# LPDDR4_SDRAM_1.net
KiCad netlist of a schematic drawn in Altium Designer
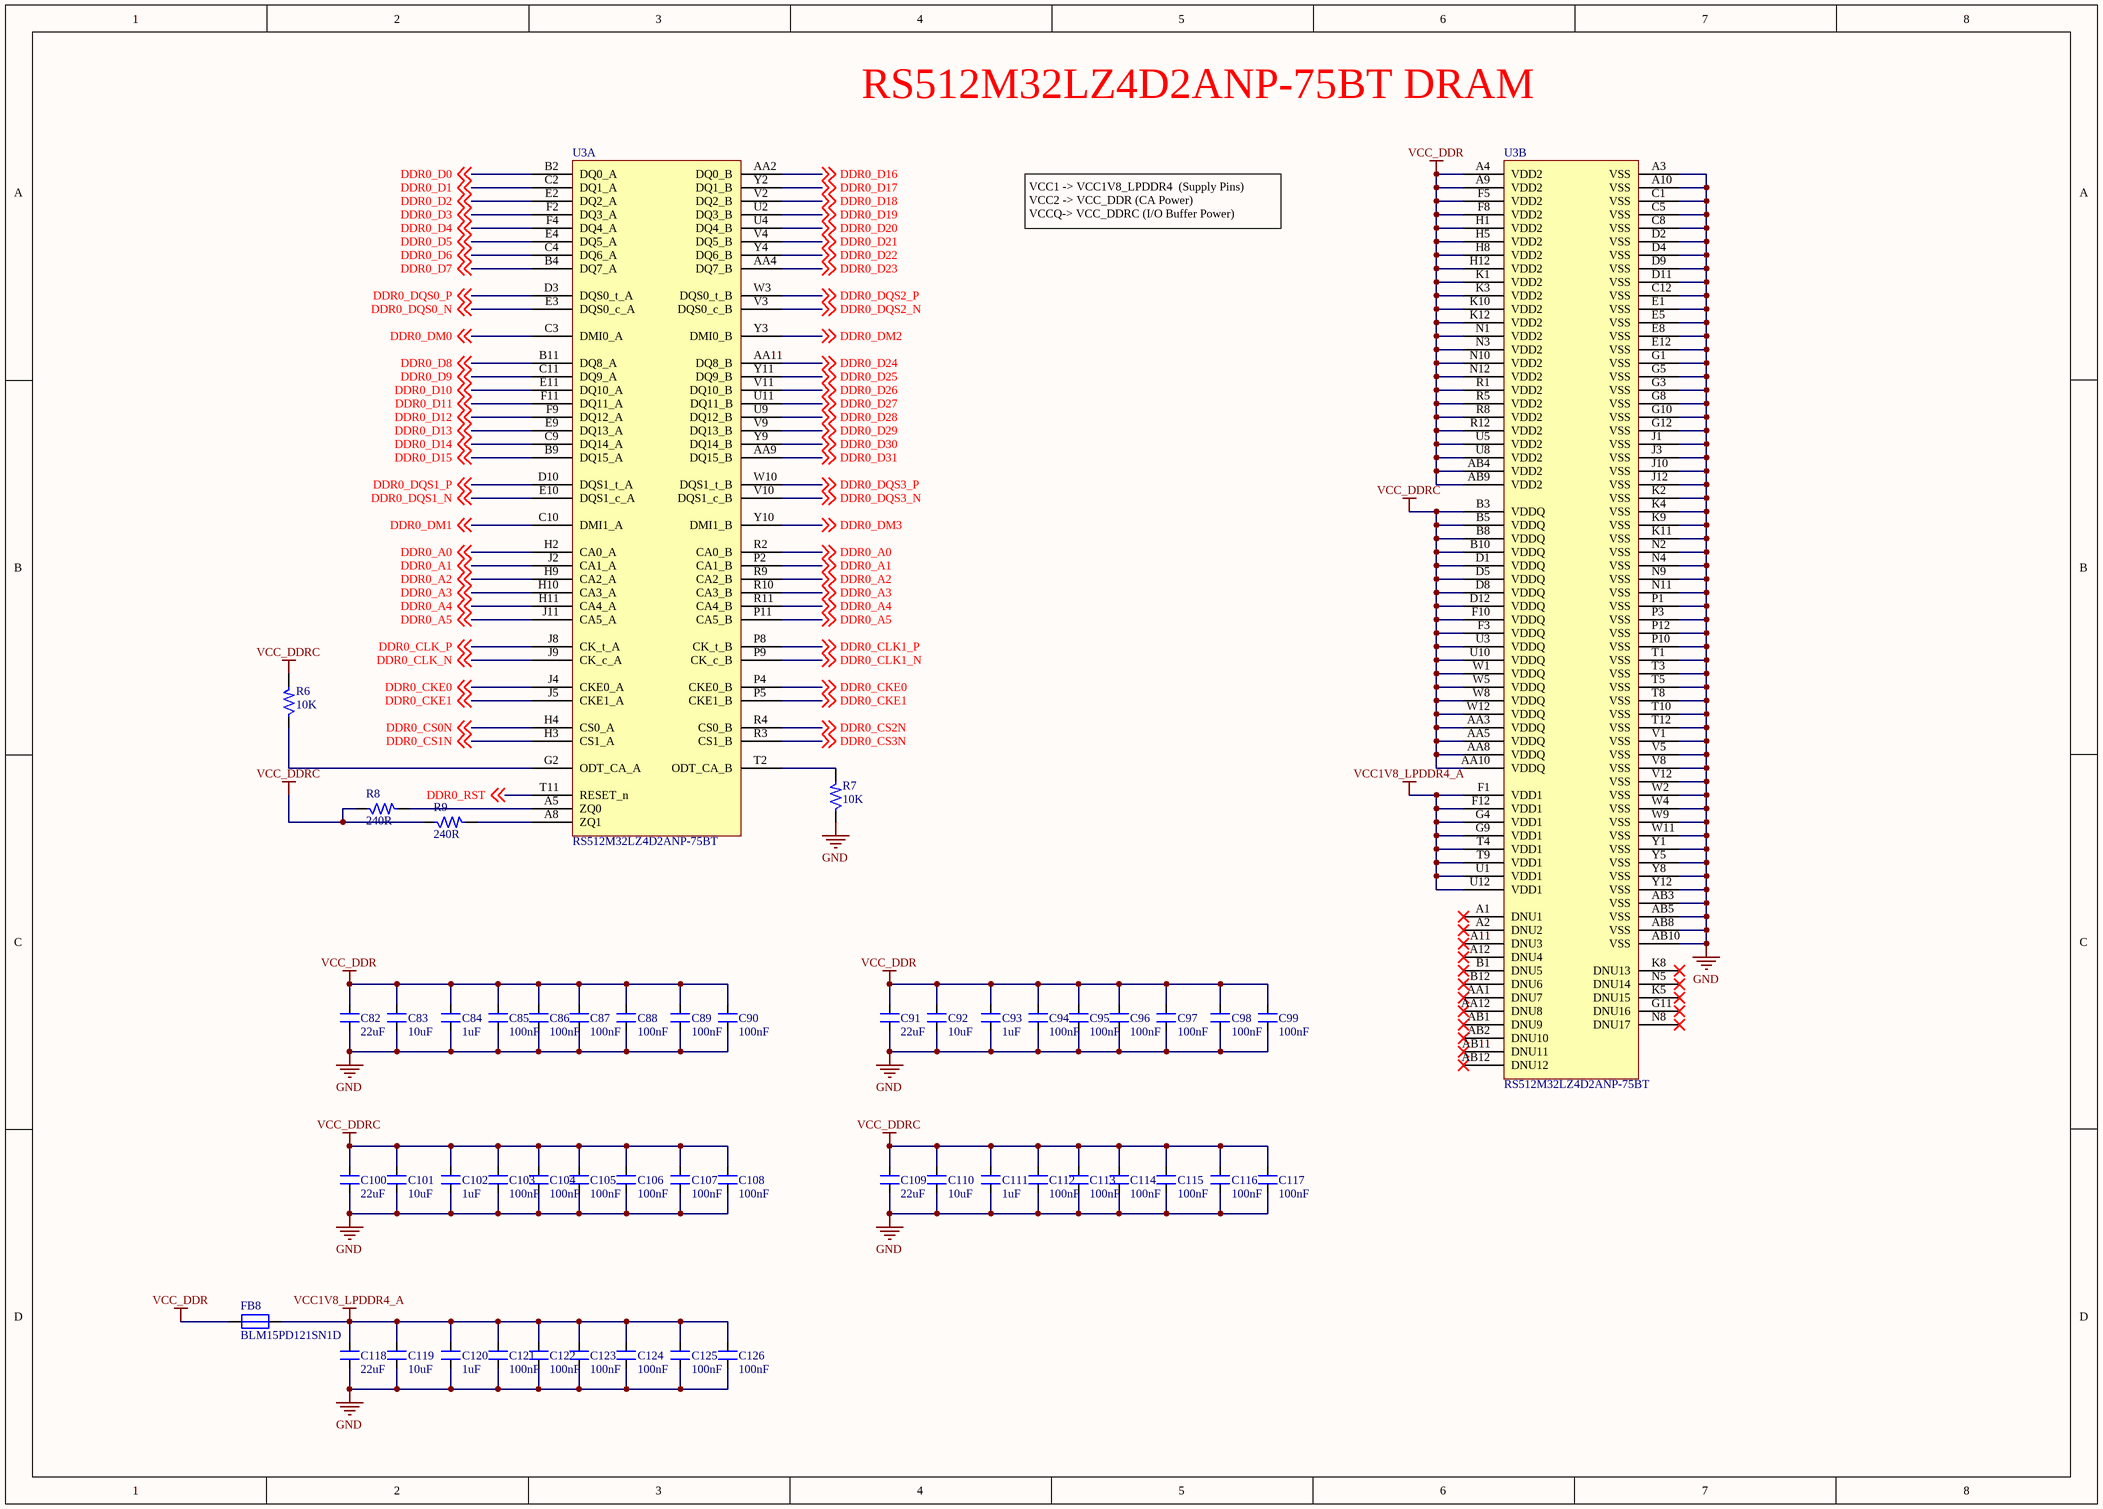
[diagram p0: LPDDR4 SDRAM_1.SchDoc]

(export (version "E")
  (design (tool "Eeschema 10.0.6"))
  (components
    (comp (ref "C82")
      (value "22uF")
      (footprint "CAP_0402")
      (description "22µF ±20% 6.3V Ceramic Capacitor X5R 0402 (1005 Metric)")
      (fields
        (field (name "MANUFACTURER") "Murata Electronics")
        (field (name "MANUFACTURER PART NUMBER") "CL05A226MQ5N6J8")
      )
      (libsource (lib "RK3399 _Module_Intlib") (part "CAP_22uF-6.3V-20%-0402"))
    )
    (comp (ref "C83")
      (value "10uF")
      (footprint "CAP_0402")
      (description "10µF ±20% 10V Ceramic Capacitor X5R 0402 (1005 Metric)")
      (fields
        (field (name "MANUFACTURER PART NUMBER") "CL05A106MP5NUNC")
        (field (name "MANUFACTURER") "Samsung Electro-Mechanics")
      )
      (libsource (lib "RK3399 _Module_Schlib") (part "CAP_10uF-10V-20%-0402"))
    )
    (comp (ref "C84")
      (value "1uF")
      (footprint "CAP_0201")
      (description "1µF ±20% 16V Ceramic Capacitor X5R 0201 (0603 Metric)")
      (fields
        (field (name "MANUFACTURER") "Samsung Electro-Mechanics")
        (field (name "MANUFACTURER PART NUMBER") "CL03A105MO3NRNH")
      )
      (libsource (lib "RK3399 _Module_Intlib") (part "CAP_1uF-16V-10%-0201"))
    )
    (comp (ref "C85")
      (value "100nF")
      (footprint "CAP_0201")
      (description "0.1µF ±10% 25V Ceramic Capacitor X5R 0201 (0603 Metric)")
      (fields
        (field (name "MANUFACTURER") "TDK Corporation")
        (field (name "MANUFACTURER PART NUMBER") "C0603X5R1E104K030BB")
      )
      (libsource (lib "RK3399 _Module_Intlib") (part "CAP_100nF-25V-10%-0201"))
    )
    (comp (ref "C86")
      (value "100nF")
      (footprint "CAP_0201")
      (description "0.1µF ±10% 25V Ceramic Capacitor X5R 0201 (0603 Metric)")
      (fields
        (field (name "MANUFACTURER") "TDK Corporation")
        (field (name "MANUFACTURER PART NUMBER") "C0603X5R1E104K030BB")
      )
      (libsource (lib "RK3399 _Module_Intlib") (part "CAP_100nF-25V-10%-0201"))
    )
    (comp (ref "C87")
      (value "100nF")
      (footprint "CAP_0201")
      (description "0.1µF ±10% 25V Ceramic Capacitor X5R 0201 (0603 Metric)")
      (fields
        (field (name "MANUFACTURER") "TDK Corporation")
        (field (name "MANUFACTURER PART NUMBER") "C0603X5R1E104K030BB")
      )
      (libsource (lib "RK3399 _Module_Intlib") (part "CAP_100nF-25V-10%-0201"))
    )
    (comp (ref "C88")
      (value "100nF")
      (footprint "CAP_0201")
      (description "0.1µF ±10% 25V Ceramic Capacitor X5R 0201 (0603 Metric)")
      (fields
        (field (name "MANUFACTURER") "TDK Corporation")
        (field (name "MANUFACTURER PART NUMBER") "C0603X5R1E104K030BB")
      )
      (libsource (lib "RK3399 _Module_Intlib") (part "CAP_100nF-25V-10%-0201"))
    )
    (comp (ref "C89")
      (value "100nF")
      (footprint "CAP_0201")
      (description "0.1µF ±10% 25V Ceramic Capacitor X5R 0201 (0603 Metric)")
      (fields
        (field (name "MANUFACTURER") "TDK Corporation")
        (field (name "MANUFACTURER PART NUMBER") "C0603X5R1E104K030BB")
      )
      (libsource (lib "RK3399 _Module_Intlib") (part "CAP_100nF-25V-10%-0201"))
    )
    (comp (ref "C90")
      (value "100nF")
      (footprint "CAP_0201")
      (description "0.1µF ±10% 25V Ceramic Capacitor X5R 0201 (0603 Metric)")
      (fields
        (field (name "MANUFACTURER") "TDK Corporation")
        (field (name "MANUFACTURER PART NUMBER") "C0603X5R1E104K030BB")
      )
      (libsource (lib "RK3399 _Module_Intlib") (part "CAP_100nF-25V-10%-0201"))
    )
    (comp (ref "C91")
      (value "22uF")
      (footprint "CAP_0402")
      (description "22µF ±20% 6.3V Ceramic Capacitor X5R 0402 (1005 Metric)")
      (fields
        (field (name "MANUFACTURER") "Murata Electronics")
        (field (name "MANUFACTURER PART NUMBER") "CL05A226MQ5N6J8")
      )
      (libsource (lib "RK3399 _Module_Intlib") (part "CAP_22uF-6.3V-20%-0402"))
    )
    (comp (ref "C92")
      (value "10uF")
      (footprint "CAP_0402")
      (description "10µF ±20% 10V Ceramic Capacitor X5R 0402 (1005 Metric)")
      (fields
        (field (name "MANUFACTURER PART NUMBER") "CL05A106MP5NUNC")
        (field (name "MANUFACTURER") "Samsung Electro-Mechanics")
      )
      (libsource (lib "RK3399 _Module_Schlib") (part "CAP_10uF-10V-20%-0402"))
    )
    (comp (ref "C93")
      (value "1uF")
      (footprint "CAP_0201")
      (description "1µF ±20% 16V Ceramic Capacitor X5R 0201 (0603 Metric)")
      (fields
        (field (name "MANUFACTURER") "Samsung Electro-Mechanics")
        (field (name "MANUFACTURER PART NUMBER") "CL03A105MO3NRNH")
      )
      (libsource (lib "RK3399 _Module_Intlib") (part "CAP_1uF-16V-10%-0201"))
    )
    (comp (ref "C94")
      (value "100nF")
      (footprint "CAP_0201")
      (description "0.1µF ±10% 25V Ceramic Capacitor X5R 0201 (0603 Metric)")
      (fields
        (field (name "MANUFACTURER") "TDK Corporation")
        (field (name "MANUFACTURER PART NUMBER") "C0603X5R1E104K030BB")
      )
      (libsource (lib "RK3399 _Module_Intlib") (part "CAP_100nF-25V-10%-0201"))
    )
    (comp (ref "C95")
      (value "100nF")
      (footprint "CAP_0201")
      (description "0.1µF ±10% 25V Ceramic Capacitor X5R 0201 (0603 Metric)")
      (fields
        (field (name "MANUFACTURER") "TDK Corporation")
        (field (name "MANUFACTURER PART NUMBER") "C0603X5R1E104K030BB")
      )
      (libsource (lib "RK3399 _Module_Intlib") (part "CAP_100nF-25V-10%-0201"))
    )
    (comp (ref "C96")
      (value "100nF")
      (footprint "CAP_0201")
      (description "0.1µF ±10% 25V Ceramic Capacitor X5R 0201 (0603 Metric)")
      (fields
        (field (name "MANUFACTURER") "TDK Corporation")
        (field (name "MANUFACTURER PART NUMBER") "C0603X5R1E104K030BB")
      )
      (libsource (lib "RK3399 _Module_Intlib") (part "CAP_100nF-25V-10%-0201"))
    )
    (comp (ref "C97")
      (value "100nF")
      (footprint "CAP_0201")
      (description "0.1µF ±10% 25V Ceramic Capacitor X5R 0201 (0603 Metric)")
      (fields
        (field (name "MANUFACTURER") "TDK Corporation")
        (field (name "MANUFACTURER PART NUMBER") "C0603X5R1E104K030BB")
      )
      (libsource (lib "RK3399 _Module_Intlib") (part "CAP_100nF-25V-10%-0201"))
    )
    (comp (ref "C98")
      (value "100nF")
      (footprint "CAP_0201")
      (description "0.1µF ±10% 25V Ceramic Capacitor X5R 0201 (0603 Metric)")
      (fields
        (field (name "MANUFACTURER") "TDK Corporation")
        (field (name "MANUFACTURER PART NUMBER") "C0603X5R1E104K030BB")
      )
      (libsource (lib "RK3399 _Module_Intlib") (part "CAP_100nF-25V-10%-0201"))
    )
    (comp (ref "C99")
      (value "100nF")
      (footprint "CAP_0201")
      (description "0.1µF ±10% 25V Ceramic Capacitor X5R 0201 (0603 Metric)")
      (fields
        (field (name "MANUFACTURER") "TDK Corporation")
        (field (name "MANUFACTURER PART NUMBER") "C0603X5R1E104K030BB")
      )
      (libsource (lib "RK3399 _Module_Intlib") (part "CAP_100nF-25V-10%-0201"))
    )
    (comp (ref "C100")
      (value "22uF")
      (footprint "CAP_0402")
      (description "22µF ±20% 6.3V Ceramic Capacitor X5R 0402 (1005 Metric)")
      (fields
        (field (name "MANUFACTURER") "Murata Electronics")
        (field (name "MANUFACTURER PART NUMBER") "CL05A226MQ5N6J8")
      )
      (libsource (lib "RK3399 _Module_Intlib") (part "CAP_22uF-6.3V-20%-0402"))
    )
    (comp (ref "C101")
      (value "10uF")
      (footprint "CAP_0402")
      (description "10µF ±20% 10V Ceramic Capacitor X5R 0402 (1005 Metric)")
      (fields
        (field (name "MANUFACTURER PART NUMBER") "CL05A106MP5NUNC")
        (field (name "MANUFACTURER") "Samsung Electro-Mechanics")
      )
      (libsource (lib "RK3399 _Module_Schlib") (part "CAP_10uF-10V-20%-0402"))
    )
    (comp (ref "C102")
      (value "1uF")
      (footprint "CAP_0201")
      (description "1µF ±20% 16V Ceramic Capacitor X5R 0201 (0603 Metric)")
      (fields
        (field (name "MANUFACTURER") "Samsung Electro-Mechanics")
        (field (name "MANUFACTURER PART NUMBER") "CL03A105MO3NRNH")
      )
      (libsource (lib "RK3399 _Module_Intlib") (part "CAP_1uF-16V-10%-0201"))
    )
    (comp (ref "C103")
      (value "100nF")
      (footprint "CAP_0201")
      (description "0.1µF ±10% 25V Ceramic Capacitor X5R 0201 (0603 Metric)")
      (fields
        (field (name "MANUFACTURER") "TDK Corporation")
        (field (name "MANUFACTURER PART NUMBER") "C0603X5R1E104K030BB")
      )
      (libsource (lib "RK3399 _Module_Intlib") (part "CAP_100nF-25V-10%-0201"))
    )
    (comp (ref "C104")
      (value "100nF")
      (footprint "CAP_0201")
      (description "0.1µF ±10% 25V Ceramic Capacitor X5R 0201 (0603 Metric)")
      (fields
        (field (name "MANUFACTURER") "TDK Corporation")
        (field (name "MANUFACTURER PART NUMBER") "C0603X5R1E104K030BB")
      )
      (libsource (lib "RK3399 _Module_Intlib") (part "CAP_100nF-25V-10%-0201"))
    )
    (comp (ref "C105")
      (value "100nF")
      (footprint "CAP_0201")
      (description "0.1µF ±10% 25V Ceramic Capacitor X5R 0201 (0603 Metric)")
      (fields
        (field (name "MANUFACTURER") "TDK Corporation")
        (field (name "MANUFACTURER PART NUMBER") "C0603X5R1E104K030BB")
      )
      (libsource (lib "RK3399 _Module_Intlib") (part "CAP_100nF-25V-10%-0201"))
    )
    (comp (ref "C106")
      (value "100nF")
      (footprint "CAP_0201")
      (description "0.1µF ±10% 25V Ceramic Capacitor X5R 0201 (0603 Metric)")
      (fields
        (field (name "MANUFACTURER") "TDK Corporation")
        (field (name "MANUFACTURER PART NUMBER") "C0603X5R1E104K030BB")
      )
      (libsource (lib "RK3399 _Module_Intlib") (part "CAP_100nF-25V-10%-0201"))
    )
    (comp (ref "C107")
      (value "100nF")
      (footprint "CAP_0201")
      (description "0.1µF ±10% 25V Ceramic Capacitor X5R 0201 (0603 Metric)")
      (fields
        (field (name "MANUFACTURER") "TDK Corporation")
        (field (name "MANUFACTURER PART NUMBER") "C0603X5R1E104K030BB")
      )
      (libsource (lib "RK3399 _Module_Intlib") (part "CAP_100nF-25V-10%-0201"))
    )
    (comp (ref "C108")
      (value "100nF")
      (footprint "CAP_0201")
      (description "0.1µF ±10% 25V Ceramic Capacitor X5R 0201 (0603 Metric)")
      (fields
        (field (name "MANUFACTURER") "TDK Corporation")
        (field (name "MANUFACTURER PART NUMBER") "C0603X5R1E104K030BB")
      )
      (libsource (lib "RK3399 _Module_Intlib") (part "CAP_100nF-25V-10%-0201"))
    )
    (comp (ref "C109")
      (value "22uF")
      (footprint "CAP_0402")
      (description "22µF ±20% 6.3V Ceramic Capacitor X5R 0402 (1005 Metric)")
      (fields
        (field (name "MANUFACTURER") "Murata Electronics")
        (field (name "MANUFACTURER PART NUMBER") "CL05A226MQ5N6J8")
      )
      (libsource (lib "RK3399 _Module_Intlib") (part "CAP_22uF-6.3V-20%-0402"))
    )
    (comp (ref "C110")
      (value "10uF")
      (footprint "CAP_0402")
      (description "10µF ±20% 10V Ceramic Capacitor X5R 0402 (1005 Metric)")
      (fields
        (field (name "MANUFACTURER PART NUMBER") "CL05A106MP5NUNC")
        (field (name "MANUFACTURER") "Samsung Electro-Mechanics")
      )
      (libsource (lib "RK3399 _Module_Schlib") (part "CAP_10uF-10V-20%-0402"))
    )
    (comp (ref "C111")
      (value "1uF")
      (footprint "CAP_0201")
      (description "1µF ±20% 16V Ceramic Capacitor X5R 0201 (0603 Metric)")
      (fields
        (field (name "MANUFACTURER") "Samsung Electro-Mechanics")
        (field (name "MANUFACTURER PART NUMBER") "CL03A105MO3NRNH")
      )
      (libsource (lib "RK3399 _Module_Intlib") (part "CAP_1uF-16V-10%-0201"))
    )
    (comp (ref "C112")
      (value "100nF")
      (footprint "CAP_0201")
      (description "0.1µF ±10% 25V Ceramic Capacitor X5R 0201 (0603 Metric)")
      (fields
        (field (name "MANUFACTURER") "TDK Corporation")
        (field (name "MANUFACTURER PART NUMBER") "C0603X5R1E104K030BB")
      )
      (libsource (lib "RK3399 _Module_Intlib") (part "CAP_100nF-25V-10%-0201"))
    )
    (comp (ref "C113")
      (value "100nF")
      (footprint "CAP_0201")
      (description "0.1µF ±10% 25V Ceramic Capacitor X5R 0201 (0603 Metric)")
      (fields
        (field (name "MANUFACTURER") "TDK Corporation")
        (field (name "MANUFACTURER PART NUMBER") "C0603X5R1E104K030BB")
      )
      (libsource (lib "RK3399 _Module_Intlib") (part "CAP_100nF-25V-10%-0201"))
    )
    (comp (ref "C114")
      (value "100nF")
      (footprint "CAP_0201")
      (description "0.1µF ±10% 25V Ceramic Capacitor X5R 0201 (0603 Metric)")
      (fields
        (field (name "MANUFACTURER") "TDK Corporation")
        (field (name "MANUFACTURER PART NUMBER") "C0603X5R1E104K030BB")
      )
      (libsource (lib "RK3399 _Module_Intlib") (part "CAP_100nF-25V-10%-0201"))
    )
    (comp (ref "C115")
      (value "100nF")
      (footprint "CAP_0201")
      (description "0.1µF ±10% 25V Ceramic Capacitor X5R 0201 (0603 Metric)")
      (fields
        (field (name "MANUFACTURER") "TDK Corporation")
        (field (name "MANUFACTURER PART NUMBER") "C0603X5R1E104K030BB")
      )
      (libsource (lib "RK3399 _Module_Intlib") (part "CAP_100nF-25V-10%-0201"))
    )
    (comp (ref "C116")
      (value "100nF")
      (footprint "CAP_0201")
      (description "0.1µF ±10% 25V Ceramic Capacitor X5R 0201 (0603 Metric)")
      (fields
        (field (name "MANUFACTURER") "TDK Corporation")
        (field (name "MANUFACTURER PART NUMBER") "C0603X5R1E104K030BB")
      )
      (libsource (lib "RK3399 _Module_Intlib") (part "CAP_100nF-25V-10%-0201"))
    )
    (comp (ref "C117")
      (value "100nF")
      (footprint "CAP_0201")
      (description "0.1µF ±10% 25V Ceramic Capacitor X5R 0201 (0603 Metric)")
      (fields
        (field (name "MANUFACTURER") "TDK Corporation")
        (field (name "MANUFACTURER PART NUMBER") "C0603X5R1E104K030BB")
      )
      (libsource (lib "RK3399 _Module_Intlib") (part "CAP_100nF-25V-10%-0201"))
    )
    (comp (ref "C118")
      (value "22uF")
      (footprint "CAP_0402")
      (description "22µF ±20% 6.3V Ceramic Capacitor X5R 0402 (1005 Metric)")
      (fields
        (field (name "MANUFACTURER") "Murata Electronics")
        (field (name "MANUFACTURER PART NUMBER") "CL05A226MQ5N6J8")
      )
      (libsource (lib "RK3399 _Module_Intlib") (part "CAP_22uF-6.3V-20%-0402"))
    )
    (comp (ref "C119")
      (value "10uF")
      (footprint "CAP_0402")
      (description "10µF ±20% 10V Ceramic Capacitor X5R 0402 (1005 Metric)")
      (fields
        (field (name "MANUFACTURER PART NUMBER") "CL05A106MP5NUNC")
        (field (name "MANUFACTURER") "Samsung Electro-Mechanics")
      )
      (libsource (lib "RK3399 _Module_Schlib") (part "CAP_10uF-10V-20%-0402"))
    )
    (comp (ref "C120")
      (value "1uF")
      (footprint "CAP_0201")
      (description "1µF ±20% 16V Ceramic Capacitor X5R 0201 (0603 Metric)")
      (fields
        (field (name "MANUFACTURER") "Samsung Electro-Mechanics")
        (field (name "MANUFACTURER PART NUMBER") "CL03A105MO3NRNH")
      )
      (libsource (lib "RK3399 _Module_Intlib") (part "CAP_1uF-16V-10%-0201"))
    )
    (comp (ref "C121")
      (value "100nF")
      (footprint "CAP_0201")
      (description "0.1µF ±10% 25V Ceramic Capacitor X5R 0201 (0603 Metric)")
      (fields
        (field (name "MANUFACTURER") "TDK Corporation")
        (field (name "MANUFACTURER PART NUMBER") "C0603X5R1E104K030BB")
      )
      (libsource (lib "RK3399 _Module_Intlib") (part "CAP_100nF-25V-10%-0201"))
    )
    (comp (ref "C122")
      (value "100nF")
      (footprint "CAP_0201")
      (description "0.1µF ±10% 25V Ceramic Capacitor X5R 0201 (0603 Metric)")
      (fields
        (field (name "MANUFACTURER") "TDK Corporation")
        (field (name "MANUFACTURER PART NUMBER") "C0603X5R1E104K030BB")
      )
      (libsource (lib "RK3399 _Module_Intlib") (part "CAP_100nF-25V-10%-0201"))
    )
    (comp (ref "C123")
      (value "100nF")
      (footprint "CAP_0201")
      (description "0.1µF ±10% 25V Ceramic Capacitor X5R 0201 (0603 Metric)")
      (fields
        (field (name "MANUFACTURER") "TDK Corporation")
        (field (name "MANUFACTURER PART NUMBER") "C0603X5R1E104K030BB")
      )
      (libsource (lib "RK3399 _Module_Intlib") (part "CAP_100nF-25V-10%-0201"))
    )
    (comp (ref "C124")
      (value "100nF")
      (footprint "CAP_0201")
      (description "0.1µF ±10% 25V Ceramic Capacitor X5R 0201 (0603 Metric)")
      (fields
        (field (name "MANUFACTURER") "TDK Corporation")
        (field (name "MANUFACTURER PART NUMBER") "C0603X5R1E104K030BB")
      )
      (libsource (lib "RK3399 _Module_Intlib") (part "CAP_100nF-25V-10%-0201"))
    )
    (comp (ref "C125")
      (value "100nF")
      (footprint "CAP_0201")
      (description "0.1µF ±10% 25V Ceramic Capacitor X5R 0201 (0603 Metric)")
      (fields
        (field (name "MANUFACTURER") "TDK Corporation")
        (field (name "MANUFACTURER PART NUMBER") "C0603X5R1E104K030BB")
      )
      (libsource (lib "RK3399 _Module_Intlib") (part "CAP_100nF-25V-10%-0201"))
    )
    (comp (ref "C126")
      (value "100nF")
      (footprint "CAP_0201")
      (description "0.1µF ±10% 25V Ceramic Capacitor X5R 0201 (0603 Metric)")
      (fields
        (field (name "MANUFACTURER") "TDK Corporation")
        (field (name "MANUFACTURER PART NUMBER") "C0603X5R1E104K030BB")
      )
      (libsource (lib "RK3399 _Module_Intlib") (part "CAP_100nF-25V-10%-0201"))
    )
    (comp (ref "FB8")
      (value "BLM15PD121SN1D")
      (footprint "RES_0402")
      (description "120 Ohms @ 100MHz 1 Power Line Ferrite Bead 0402 (1005 Metric) 1.3A 90mOhm")
      (fields (field (name "MANUFACTURER") "Murata Electronics"))
      (libsource (lib "RK3399 _Module_Schlib") (part "FB_120R-1.3A-100Mhz-0402"))
    )
    (comp (ref "R6")
      (value "10K")
      (footprint "RES_0201")
      (description "10 kOhms ±1% 0.05W, 1/20W Chip Resistor 0201 (0603 Metric) Thick Film")
      (fields
        (field (name "MANUFACTURER") "Stackpole Electronics Inc")
        (field (name "MANUFACTURER PART NUMBER") "RMCF0201FT10K0")
      )
      (libsource (lib "RK3399 _Module_Intlib") (part "RES_10K-0.05W-1%-0201"))
    )
    (comp (ref "R7")
      (value "10K")
      (footprint "RES_0201")
      (description "10 kOhms ±1% 0.05W, 1/20W Chip Resistor 0201 (0603 Metric) Thick Film")
      (fields
        (field (name "MANUFACTURER") "Stackpole Electronics Inc")
        (field (name "MANUFACTURER PART NUMBER") "RMCF0201FT10K0")
      )
      (libsource (lib "RK3399 _Module_Intlib") (part "RES_10K-0.05W-1%-0201"))
    )
    (comp (ref "R8")
      (value "240R")
      (footprint "RES_0201")
      (description "240 Ohms ±1% 0.05W, 1/20W Chip Resistor 0201 (0603 Metric) Thick Film")
      (fields
        (field (name "MANUFACTURER") "Yageo")
        (field (name "MANUFACTURER PART NUMBER") "RC0201FR-07240RL")
      )
      (libsource (lib "RK3399 _Module_Intlib") (part "RES_240R-0.05W-1%-0201"))
    )
    (comp (ref "R9")
      (value "240R")
      (footprint "RES_0201")
      (description "240 Ohms ±1% 0.05W, 1/20W Chip Resistor 0201 (0603 Metric) Thick Film")
      (fields
        (field (name "MANUFACTURER") "Yageo")
        (field (name "MANUFACTURER PART NUMBER") "RC0201FR-07240RL")
      )
      (libsource (lib "RK3399 _Module_Intlib") (part "RES_240R-0.05W-1%-0201"))
    )
    (comp (ref "U3")
      (value "RS512M32LZ4D2ANP-75BT")
      (footprint "FBGA200_SMD")
      (fields (field (name "MANUFACTURER") "RAYSON"))
      (libsource (lib "RK3399 _Module_Schlib") (part "IC_RS512M32LZ4D2ANP-75BT"))
    )
  )
  (nets
    (net (code "1") (name "DDR0_A0") (class "Default")
      (node (ref "U3") (pin "H2") (pinfunction "CA0_A_H2") (pintype "passive"))
      (node (ref "U3") (pin "R2") (pinfunction "CA0_B_R2") (pintype "passive"))
    )
    (net (code "2") (name "DDR0_A1") (class "Default")
      (node (ref "U3") (pin "J2") (pinfunction "CA1_A_J2") (pintype "passive"))
      (node (ref "U3") (pin "P2") (pinfunction "CA1_B_P2") (pintype "passive"))
    )
    (net (code "3") (name "DDR0_A2") (class "Default")
      (node (ref "U3") (pin "H9") (pinfunction "CA2_A_H9") (pintype "passive"))
      (node (ref "U3") (pin "R9") (pinfunction "CA2_B_R9") (pintype "passive"))
    )
    (net (code "4") (name "DDR0_A3") (class "Default")
      (node (ref "U3") (pin "H10") (pinfunction "CA3_A_H10") (pintype "passive"))
      (node (ref "U3") (pin "R10") (pinfunction "CA3_B_R10") (pintype "passive"))
    )
    (net (code "5") (name "DDR0_A4") (class "Default")
      (node (ref "U3") (pin "H11") (pinfunction "CA4_A_H11") (pintype "passive"))
      (node (ref "U3") (pin "R11") (pinfunction "CA4_B_R11") (pintype "passive"))
    )
    (net (code "6") (name "DDR0_A5") (class "Default")
      (node (ref "U3") (pin "J11") (pinfunction "CA5_A_J11") (pintype "passive"))
      (node (ref "U3") (pin "P11") (pinfunction "CA5_B_P11") (pintype "passive"))
    )
    (net (code "7") (name "DDR0_CKE0") (class "Default")
      (node (ref "U3") (pin "J4") (pinfunction "CKE0_A_J4") (pintype "passive"))
      (node (ref "U3") (pin "P4") (pinfunction "CKE0_B_P4") (pintype "passive"))
    )
    (net (code "8") (name "DDR0_CKE1") (class "Default")
      (node (ref "U3") (pin "J5") (pinfunction "CKE1_A_J5") (pintype "passive"))
      (node (ref "U3") (pin "P5") (pinfunction "CKE1_B_P5") (pintype "passive"))
    )
    (net (code "9") (name "DDR0_CLK1_N") (class "Default")
      (node (ref "U3") (pin "P9") (pinfunction "CK_c_B_P9") (pintype "passive"))
    )
    (net (code "10") (name "DDR0_CLK1_P") (class "Default")
      (node (ref "U3") (pin "P8") (pinfunction "CK_t_B_P8") (pintype "passive"))
    )
    (net (code "11") (name "DDR0_CLK_N") (class "Default")
      (node (ref "U3") (pin "J9") (pinfunction "CK_c_A_J9") (pintype "passive"))
    )
    (net (code "12") (name "DDR0_CLK_P") (class "Default")
      (node (ref "U3") (pin "J8") (pinfunction "CK_t_A_J8") (pintype "passive"))
    )
    (net (code "13") (name "DDR0_CS0N") (class "Default")
      (node (ref "U3") (pin "H4") (pinfunction "CS0_A_H4") (pintype "passive"))
    )
    (net (code "14") (name "DDR0_CS1N") (class "Default")
      (node (ref "U3") (pin "H3") (pinfunction "CS1_A_H3") (pintype "passive"))
    )
    (net (code "15") (name "DDR0_CS2N") (class "Default")
      (node (ref "U3") (pin "R4") (pinfunction "CS0_B_R4") (pintype "passive"))
    )
    (net (code "16") (name "DDR0_CS3N") (class "Default")
      (node (ref "U3") (pin "R3") (pinfunction "CS1_B_R3") (pintype "passive"))
    )
    (net (code "17") (name "DDR0_D0") (class "Default")
      (node (ref "U3") (pin "B2") (pinfunction "DQ0_A_B2") (pintype "passive"))
    )
    (net (code "18") (name "DDR0_D1") (class "Default")
      (node (ref "U3") (pin "C2") (pinfunction "DQ1_A_C2") (pintype "passive"))
    )
    (net (code "19") (name "DDR0_D2") (class "Default")
      (node (ref "U3") (pin "E2") (pinfunction "DQ2_A_E2") (pintype "passive"))
    )
    (net (code "20") (name "DDR0_D3") (class "Default")
      (node (ref "U3") (pin "F2") (pinfunction "DQ3_A_F2") (pintype "passive"))
    )
    (net (code "21") (name "DDR0_D4") (class "Default")
      (node (ref "U3") (pin "F4") (pinfunction "DQ4_A_F4") (pintype "passive"))
    )
    (net (code "22") (name "DDR0_D5") (class "Default")
      (node (ref "U3") (pin "E4") (pinfunction "DQ5_A_E4") (pintype "passive"))
    )
    (net (code "23") (name "DDR0_D6") (class "Default")
      (node (ref "U3") (pin "C4") (pinfunction "DQ6_A_C4") (pintype "passive"))
    )
    (net (code "24") (name "DDR0_D7") (class "Default")
      (node (ref "U3") (pin "B4") (pinfunction "DQ7_A_B4") (pintype "passive"))
    )
    (net (code "25") (name "DDR0_D8") (class "Default")
      (node (ref "U3") (pin "B11") (pinfunction "DQ8_A_B11") (pintype "passive"))
    )
    (net (code "26") (name "DDR0_D9") (class "Default")
      (node (ref "U3") (pin "C11") (pinfunction "DQ9_A_C11") (pintype "passive"))
    )
    (net (code "27") (name "DDR0_D10") (class "Default")
      (node (ref "U3") (pin "E11") (pinfunction "DQ10_A_E11") (pintype "passive"))
    )
    (net (code "28") (name "DDR0_D11") (class "Default")
      (node (ref "U3") (pin "F11") (pinfunction "DQ11_A_F11") (pintype "passive"))
    )
    (net (code "29") (name "DDR0_D12") (class "Default")
      (node (ref "U3") (pin "F9") (pinfunction "DQ12_A_F9") (pintype "passive"))
    )
    (net (code "30") (name "DDR0_D13") (class "Default")
      (node (ref "U3") (pin "E9") (pinfunction "DQ13_A_E9") (pintype "passive"))
    )
    (net (code "31") (name "DDR0_D14") (class "Default")
      (node (ref "U3") (pin "C9") (pinfunction "DQ14_A_C9") (pintype "passive"))
    )
    (net (code "32") (name "DDR0_D15") (class "Default")
      (node (ref "U3") (pin "B9") (pinfunction "DQ15_A_B9") (pintype "passive"))
    )
    (net (code "33") (name "DDR0_D16") (class "Default")
      (node (ref "U3") (pin "AA2") (pinfunction "DQ0_B_AA2") (pintype "passive"))
    )
    (net (code "34") (name "DDR0_D17") (class "Default")
      (node (ref "U3") (pin "Y2") (pinfunction "DQ1_B_Y2") (pintype "passive"))
    )
    (net (code "35") (name "DDR0_D18") (class "Default")
      (node (ref "U3") (pin "V2") (pinfunction "DQ2_B_V2") (pintype "passive"))
    )
    (net (code "36") (name "DDR0_D19") (class "Default")
      (node (ref "U3") (pin "U2") (pinfunction "DQ3_B_U2") (pintype "passive"))
    )
    (net (code "37") (name "DDR0_D20") (class "Default")
      (node (ref "U3") (pin "U4") (pinfunction "DQ4_B_U4") (pintype "passive"))
    )
    (net (code "38") (name "DDR0_D21") (class "Default")
      (node (ref "U3") (pin "V4") (pinfunction "DQ5_B_V4") (pintype "passive"))
    )
    (net (code "39") (name "DDR0_D22") (class "Default")
      (node (ref "U3") (pin "Y4") (pinfunction "DQ6_B_Y4") (pintype "passive"))
    )
    (net (code "40") (name "DDR0_D23") (class "Default")
      (node (ref "U3") (pin "AA4") (pinfunction "DQ7_B_AA4") (pintype "passive"))
    )
    (net (code "41") (name "DDR0_D24") (class "Default")
      (node (ref "U3") (pin "AA11") (pinfunction "DQ8_B_AA11") (pintype "passive"))
    )
    (net (code "42") (name "DDR0_D25") (class "Default")
      (node (ref "U3") (pin "Y11") (pinfunction "DQ9_B_Y11") (pintype "passive"))
    )
    (net (code "43") (name "DDR0_D26") (class "Default")
      (node (ref "U3") (pin "V11") (pinfunction "DQ10_B_V11") (pintype "passive"))
    )
    (net (code "44") (name "DDR0_D27") (class "Default")
      (node (ref "U3") (pin "U11") (pinfunction "DQ11_B_U11") (pintype "passive"))
    )
    (net (code "45") (name "DDR0_D28") (class "Default")
      (node (ref "U3") (pin "U9") (pinfunction "DQ12_B_U9") (pintype "passive"))
    )
    (net (code "46") (name "DDR0_D29") (class "Default")
      (node (ref "U3") (pin "V9") (pinfunction "DQ13_B_V9") (pintype "passive"))
    )
    (net (code "47") (name "DDR0_D30") (class "Default")
      (node (ref "U3") (pin "Y9") (pinfunction "DQ14_B_Y9") (pintype "passive"))
    )
    (net (code "48") (name "DDR0_D31") (class "Default")
      (node (ref "U3") (pin "AA9") (pinfunction "DQ15_B_AA9") (pintype "passive"))
    )
    (net (code "49") (name "DDR0_DM0") (class "Default")
      (node (ref "U3") (pin "C3") (pinfunction "DMI0_A_C3") (pintype "passive"))
    )
    (net (code "50") (name "DDR0_DM1") (class "Default")
      (node (ref "U3") (pin "C10") (pinfunction "DMI1_A_C10") (pintype "passive"))
    )
    (net (code "51") (name "DDR0_DM2") (class "Default")
      (node (ref "U3") (pin "Y3") (pinfunction "DMI0_B_Y3") (pintype "passive"))
    )
    (net (code "52") (name "DDR0_DM3") (class "Default")
      (node (ref "U3") (pin "Y10") (pinfunction "DMI1_B_Y10") (pintype "passive"))
    )
    (net (code "53") (name "DDR0_DQS0_N") (class "Default")
      (node (ref "U3") (pin "E3") (pinfunction "DQS0_c_A_E3") (pintype "passive"))
    )
    (net (code "54") (name "DDR0_DQS0_P") (class "Default")
      (node (ref "U3") (pin "D3") (pinfunction "DQS0_t_A_D3") (pintype "passive"))
    )
    (net (code "55") (name "DDR0_DQS1_N") (class "Default")
      (node (ref "U3") (pin "E10") (pinfunction "DQS1_c_A_E10") (pintype "passive"))
    )
    (net (code "56") (name "DDR0_DQS1_P") (class "Default")
      (node (ref "U3") (pin "D10") (pinfunction "DQS1_t_A_D10") (pintype "passive"))
    )
    (net (code "57") (name "DDR0_DQS2_N") (class "Default")
      (node (ref "U3") (pin "V3") (pinfunction "DQS0_c_B_V3") (pintype "passive"))
    )
    (net (code "58") (name "DDR0_DQS2_P") (class "Default")
      (node (ref "U3") (pin "W3") (pinfunction "DQS0_t_B_W3") (pintype "passive"))
    )
    (net (code "59") (name "DDR0_DQS3_N") (class "Default")
      (node (ref "U3") (pin "V10") (pinfunction "DQS1_c_B_V10") (pintype "passive"))
    )
    (net (code "60") (name "DDR0_DQS3_P") (class "Default")
      (node (ref "U3") (pin "W10") (pinfunction "DQS1_t_B_W10") (pintype "passive"))
    )
    (net (code "61") (name "DDR0_RST") (class "Default")
      (node (ref "U3") (pin "T11") (pinfunction "RESET_n_T11") (pintype "passive"))
    )
    (net (code "62") (name "GND") (class "Default")
      (node (ref "C100") (pin "1") (pinfunction "1_1") (pintype "passive"))
      (node (ref "C101") (pin "1") (pinfunction "1_1") (pintype "passive"))
      (node (ref "C102") (pin "1") (pinfunction "1_1") (pintype "passive"))
      (node (ref "C103") (pin "1") (pinfunction "1_1") (pintype "passive"))
      (node (ref "C104") (pin "1") (pinfunction "1_1") (pintype "passive"))
      (node (ref "C105") (pin "1") (pinfunction "1_1") (pintype "passive"))
      (node (ref "C106") (pin "1") (pinfunction "1_1") (pintype "passive"))
      (node (ref "C107") (pin "1") (pinfunction "1_1") (pintype "passive"))
      (node (ref "C108") (pin "1") (pinfunction "1_1") (pintype "passive"))
      (node (ref "C109") (pin "1") (pinfunction "1_1") (pintype "passive"))
      (node (ref "C110") (pin "1") (pinfunction "1_1") (pintype "passive"))
      (node (ref "C111") (pin "1") (pinfunction "1_1") (pintype "passive"))
      (node (ref "C112") (pin "1") (pinfunction "1_1") (pintype "passive"))
      (node (ref "C113") (pin "1") (pinfunction "1_1") (pintype "passive"))
      (node (ref "C114") (pin "1") (pinfunction "1_1") (pintype "passive"))
      (node (ref "C115") (pin "1") (pinfunction "1_1") (pintype "passive"))
      (node (ref "C116") (pin "1") (pinfunction "1_1") (pintype "passive"))
      (node (ref "C117") (pin "1") (pinfunction "1_1") (pintype "passive"))
      (node (ref "C118") (pin "1") (pinfunction "1_1") (pintype "passive"))
      (node (ref "C119") (pin "1") (pinfunction "1_1") (pintype "passive"))
      (node (ref "C120") (pin "1") (pinfunction "1_1") (pintype "passive"))
      (node (ref "C121") (pin "1") (pinfunction "1_1") (pintype "passive"))
      (node (ref "C122") (pin "1") (pinfunction "1_1") (pintype "passive"))
      (node (ref "C123") (pin "1") (pinfunction "1_1") (pintype "passive"))
      (node (ref "C124") (pin "1") (pinfunction "1_1") (pintype "passive"))
      (node (ref "C125") (pin "1") (pinfunction "1_1") (pintype "passive"))
      (node (ref "C126") (pin "1") (pinfunction "1_1") (pintype "passive"))
      (node (ref "C82") (pin "1") (pinfunction "1_1") (pintype "passive"))
      (node (ref "C83") (pin "1") (pinfunction "1_1") (pintype "passive"))
      (node (ref "C84") (pin "1") (pinfunction "1_1") (pintype "passive"))
      (node (ref "C85") (pin "1") (pinfunction "1_1") (pintype "passive"))
      (node (ref "C86") (pin "1") (pinfunction "1_1") (pintype "passive"))
      (node (ref "C87") (pin "1") (pinfunction "1_1") (pintype "passive"))
      (node (ref "C88") (pin "1") (pinfunction "1_1") (pintype "passive"))
      (node (ref "C89") (pin "1") (pinfunction "1_1") (pintype "passive"))
      (node (ref "C90") (pin "1") (pinfunction "1_1") (pintype "passive"))
      (node (ref "C91") (pin "1") (pinfunction "1_1") (pintype "passive"))
      (node (ref "C92") (pin "1") (pinfunction "1_1") (pintype "passive"))
      (node (ref "C93") (pin "1") (pinfunction "1_1") (pintype "passive"))
      (node (ref "C94") (pin "1") (pinfunction "1_1") (pintype "passive"))
      (node (ref "C95") (pin "1") (pinfunction "1_1") (pintype "passive"))
      (node (ref "C96") (pin "1") (pinfunction "1_1") (pintype "passive"))
      (node (ref "C97") (pin "1") (pinfunction "1_1") (pintype "passive"))
      (node (ref "C98") (pin "1") (pinfunction "1_1") (pintype "passive"))
      (node (ref "C99") (pin "1") (pinfunction "1_1") (pintype "passive"))
      (node (ref "R7") (pin "1") (pinfunction "1_1") (pintype "passive"))
      (node (ref "U3") (pin "A10") (pinfunction "VSS_A10") (pintype "passive"))
      (node (ref "U3") (pin "A3") (pinfunction "VSS_A3") (pintype "passive"))
      (node (ref "U3") (pin "AB10") (pinfunction "VSS_AB10") (pintype "passive"))
      (node (ref "U3") (pin "AB3") (pinfunction "VSS_AB3") (pintype "passive"))
      (node (ref "U3") (pin "AB5") (pinfunction "VSS_AB5") (pintype "passive"))
      (node (ref "U3") (pin "AB8") (pinfunction "VSS_AB8") (pintype "passive"))
      (node (ref "U3") (pin "C1") (pinfunction "VSS_C1") (pintype "passive"))
      (node (ref "U3") (pin "C12") (pinfunction "VSS_C12") (pintype "passive"))
      (node (ref "U3") (pin "C5") (pinfunction "VSS_C5") (pintype "passive"))
      (node (ref "U3") (pin "C8") (pinfunction "VSS_C8") (pintype "passive"))
      (node (ref "U3") (pin "D11") (pinfunction "VSS_D11") (pintype "passive"))
      (node (ref "U3") (pin "D2") (pinfunction "VSS_D2") (pintype "passive"))
      (node (ref "U3") (pin "D4") (pinfunction "VSS_D4") (pintype "passive"))
      (node (ref "U3") (pin "D9") (pinfunction "VSS_D9") (pintype "passive"))
      (node (ref "U3") (pin "E1") (pinfunction "VSS_E1") (pintype "passive"))
      (node (ref "U3") (pin "E12") (pinfunction "VSS_E12") (pintype "passive"))
      (node (ref "U3") (pin "E5") (pinfunction "VSS_E5") (pintype "passive"))
      (node (ref "U3") (pin "E8") (pinfunction "VSS_E8") (pintype "passive"))
      (node (ref "U3") (pin "G1") (pinfunction "VSS_G1") (pintype "passive"))
      (node (ref "U3") (pin "G10") (pinfunction "VSS_G10") (pintype "passive"))
      (node (ref "U3") (pin "G12") (pinfunction "VSS_G12") (pintype "passive"))
      (node (ref "U3") (pin "G3") (pinfunction "VSS_G3") (pintype "passive"))
      (node (ref "U3") (pin "G5") (pinfunction "VSS_G5") (pintype "passive"))
      (node (ref "U3") (pin "G8") (pinfunction "VSS_G8") (pintype "passive"))
      (node (ref "U3") (pin "J1") (pinfunction "VSS_J1") (pintype "passive"))
      (node (ref "U3") (pin "J10") (pinfunction "VSS_J10") (pintype "passive"))
      (node (ref "U3") (pin "J12") (pinfunction "VSS_J12") (pintype "passive"))
      (node (ref "U3") (pin "J3") (pinfunction "VSS_J3") (pintype "passive"))
      (node (ref "U3") (pin "K11") (pinfunction "VSS_K11") (pintype "passive"))
      (node (ref "U3") (pin "K2") (pinfunction "VSS_K2") (pintype "passive"))
      (node (ref "U3") (pin "K4") (pinfunction "VSS_K4") (pintype "passive"))
      (node (ref "U3") (pin "K9") (pinfunction "VSS_K9") (pintype "passive"))
      (node (ref "U3") (pin "N11") (pinfunction "VSS_N11") (pintype "passive"))
      (node (ref "U3") (pin "N2") (pinfunction "VSS_N2") (pintype "passive"))
      (node (ref "U3") (pin "N4") (pinfunction "VSS_N4") (pintype "passive"))
      (node (ref "U3") (pin "N9") (pinfunction "VSS_N9") (pintype "passive"))
      (node (ref "U3") (pin "P1") (pinfunction "VSS_P1") (pintype "passive"))
      (node (ref "U3") (pin "P10") (pinfunction "VSS_P10") (pintype "passive"))
      (node (ref "U3") (pin "P12") (pinfunction "VSS_P12") (pintype "passive"))
      (node (ref "U3") (pin "P3") (pinfunction "VSS_P3") (pintype "passive"))
      (node (ref "U3") (pin "T1") (pinfunction "VSS_T1") (pintype "passive"))
      (node (ref "U3") (pin "T10") (pinfunction "VSS_T10") (pintype "passive"))
      (node (ref "U3") (pin "T12") (pinfunction "VSS_T12") (pintype "passive"))
      (node (ref "U3") (pin "T3") (pinfunction "VSS_T3") (pintype "passive"))
      (node (ref "U3") (pin "T5") (pinfunction "VSS_T5") (pintype "passive"))
      (node (ref "U3") (pin "T8") (pinfunction "VSS_T8") (pintype "passive"))
      (node (ref "U3") (pin "V1") (pinfunction "VSS_V1") (pintype "passive"))
      (node (ref "U3") (pin "V12") (pinfunction "VSS_V12") (pintype "passive"))
      (node (ref "U3") (pin "V5") (pinfunction "VSS_V5") (pintype "passive"))
      (node (ref "U3") (pin "V8") (pinfunction "VSS_V8") (pintype "passive"))
      (node (ref "U3") (pin "W11") (pinfunction "VSS_W11") (pintype "passive"))
      (node (ref "U3") (pin "W2") (pinfunction "VSS_W2") (pintype "passive"))
      (node (ref "U3") (pin "W4") (pinfunction "VSS_W4") (pintype "passive"))
      (node (ref "U3") (pin "W9") (pinfunction "VSS_W9") (pintype "passive"))
      (node (ref "U3") (pin "Y1") (pinfunction "VSS_Y1") (pintype "passive"))
      (node (ref "U3") (pin "Y12") (pinfunction "VSS_Y12") (pintype "passive"))
      (node (ref "U3") (pin "Y5") (pinfunction "VSS_Y5") (pintype "passive"))
      (node (ref "U3") (pin "Y8") (pinfunction "VSS_Y8") (pintype "passive"))
    )
    (net (code "63") (name "Net-(U3A-ODT_CA_A)") (class "Default")
      (node (ref "R6") (pin "1") (pinfunction "1_1") (pintype "passive"))
      (node (ref "U3") (pin "G2") (pinfunction "ODT_CA_A_G2") (pintype "passive"))
    )
    (net (code "64") (name "Net-(U3A-ODT_CA_B)") (class "Default")
      (node (ref "R7") (pin "2") (pinfunction "2_2") (pintype "passive"))
      (node (ref "U3") (pin "T2") (pinfunction "ODT_CA_B_T2") (pintype "passive"))
    )
    (net (code "65") (name "Net-(U3A-ZQ0)") (class "Default")
      (node (ref "R8") (pin "2") (pinfunction "2_2") (pintype "passive"))
      (node (ref "U3") (pin "A5") (pinfunction "ZQ0_A5") (pintype "passive"))
    )
    (net (code "66") (name "Net-(U3A-ZQ1)") (class "Default")
      (node (ref "R9") (pin "2") (pinfunction "2_2") (pintype "passive"))
      (node (ref "U3") (pin "A8") (pinfunction "ZQ1_A8") (pintype "passive"))
    )
    (net (code "67") (name "VCC1V8_LPDDR4_A") (class "Default")
      (node (ref "C118") (pin "2") (pinfunction "2_2") (pintype "passive"))
      (node (ref "C119") (pin "2") (pinfunction "2_2") (pintype "passive"))
      (node (ref "C120") (pin "2") (pinfunction "2_2") (pintype "passive"))
      (node (ref "C121") (pin "2") (pinfunction "2_2") (pintype "passive"))
      (node (ref "C122") (pin "2") (pinfunction "2_2") (pintype "passive"))
      (node (ref "C123") (pin "2") (pinfunction "2_2") (pintype "passive"))
      (node (ref "C124") (pin "2") (pinfunction "2_2") (pintype "passive"))
      (node (ref "C125") (pin "2") (pinfunction "2_2") (pintype "passive"))
      (node (ref "C126") (pin "2") (pinfunction "2_2") (pintype "passive"))
      (node (ref "FB8") (pin "2") (pinfunction "2_2") (pintype "passive"))
      (node (ref "U3") (pin "F1") (pinfunction "VDD1_F1") (pintype "passive"))
      (node (ref "U3") (pin "F12") (pinfunction "VDD1_F12") (pintype "passive"))
      (node (ref "U3") (pin "G4") (pinfunction "VDD1_G4") (pintype "passive"))
      (node (ref "U3") (pin "G9") (pinfunction "VDD1_G9") (pintype "passive"))
      (node (ref "U3") (pin "T4") (pinfunction "VDD1_T4") (pintype "passive"))
      (node (ref "U3") (pin "T9") (pinfunction "VDD1_T9") (pintype "passive"))
      (node (ref "U3") (pin "U1") (pinfunction "VDD1_U1") (pintype "passive"))
      (node (ref "U3") (pin "U12") (pinfunction "VDD1_U12") (pintype "passive"))
    )
    (net (code "68") (name "VCC_DDR") (class "Default")
      (node (ref "C82") (pin "2") (pinfunction "2_2") (pintype "passive"))
      (node (ref "C83") (pin "2") (pinfunction "2_2") (pintype "passive"))
      (node (ref "C84") (pin "2") (pinfunction "2_2") (pintype "passive"))
      (node (ref "C85") (pin "2") (pinfunction "2_2") (pintype "passive"))
      (node (ref "C86") (pin "2") (pinfunction "2_2") (pintype "passive"))
      (node (ref "C87") (pin "2") (pinfunction "2_2") (pintype "passive"))
      (node (ref "C88") (pin "2") (pinfunction "2_2") (pintype "passive"))
      (node (ref "C89") (pin "2") (pinfunction "2_2") (pintype "passive"))
      (node (ref "C90") (pin "2") (pinfunction "2_2") (pintype "passive"))
      (node (ref "C91") (pin "2") (pinfunction "2_2") (pintype "passive"))
      (node (ref "C92") (pin "2") (pinfunction "2_2") (pintype "passive"))
      (node (ref "C93") (pin "2") (pinfunction "2_2") (pintype "passive"))
      (node (ref "C94") (pin "2") (pinfunction "2_2") (pintype "passive"))
      (node (ref "C95") (pin "2") (pinfunction "2_2") (pintype "passive"))
      (node (ref "C96") (pin "2") (pinfunction "2_2") (pintype "passive"))
      (node (ref "C97") (pin "2") (pinfunction "2_2") (pintype "passive"))
      (node (ref "C98") (pin "2") (pinfunction "2_2") (pintype "passive"))
      (node (ref "C99") (pin "2") (pinfunction "2_2") (pintype "passive"))
      (node (ref "FB8") (pin "1") (pinfunction "1_1") (pintype "passive"))
      (node (ref "U3") (pin "A4") (pinfunction "VDD2_A4") (pintype "passive"))
      (node (ref "U3") (pin "A9") (pinfunction "VDD2_A9") (pintype "passive"))
      (node (ref "U3") (pin "AB4") (pinfunction "VDD2_AB4") (pintype "passive"))
      (node (ref "U3") (pin "AB9") (pinfunction "VDD2_AB9") (pintype "passive"))
      (node (ref "U3") (pin "F5") (pinfunction "VDD2_F5") (pintype "passive"))
      (node (ref "U3") (pin "F8") (pinfunction "VDD2_F8") (pintype "passive"))
      (node (ref "U3") (pin "H1") (pinfunction "VDD2_H1") (pintype "passive"))
      (node (ref "U3") (pin "H12") (pinfunction "VDD2_H12") (pintype "passive"))
      (node (ref "U3") (pin "H5") (pinfunction "VDD2_H5") (pintype "passive"))
      (node (ref "U3") (pin "H8") (pinfunction "VDD2_H8") (pintype "passive"))
      (node (ref "U3") (pin "K1") (pinfunction "VDD2_K1") (pintype "passive"))
      (node (ref "U3") (pin "K10") (pinfunction "VDD2_K10") (pintype "passive"))
      (node (ref "U3") (pin "K12") (pinfunction "VDD2_K12") (pintype "passive"))
      (node (ref "U3") (pin "K3") (pinfunction "VDD2_K3") (pintype "passive"))
      (node (ref "U3") (pin "N1") (pinfunction "VDD2_N1") (pintype "passive"))
      (node (ref "U3") (pin "N10") (pinfunction "VDD2_N10") (pintype "passive"))
      (node (ref "U3") (pin "N12") (pinfunction "VDD2_N12") (pintype "passive"))
      (node (ref "U3") (pin "N3") (pinfunction "VDD2_N3") (pintype "passive"))
      (node (ref "U3") (pin "R1") (pinfunction "VDD2_R1") (pintype "passive"))
      (node (ref "U3") (pin "R12") (pinfunction "VDD2_R12") (pintype "passive"))
      (node (ref "U3") (pin "R5") (pinfunction "VDD2_R5") (pintype "passive"))
      (node (ref "U3") (pin "R8") (pinfunction "VDD2_R8") (pintype "passive"))
      (node (ref "U3") (pin "U5") (pinfunction "VDD2_U5") (pintype "passive"))
      (node (ref "U3") (pin "U8") (pinfunction "VDD2_U8") (pintype "passive"))
    )
    (net (code "69") (name "VCC_DDRC") (class "Default")
      (node (ref "C100") (pin "2") (pinfunction "2_2") (pintype "passive"))
      (node (ref "C101") (pin "2") (pinfunction "2_2") (pintype "passive"))
      (node (ref "C102") (pin "2") (pinfunction "2_2") (pintype "passive"))
      (node (ref "C103") (pin "2") (pinfunction "2_2") (pintype "passive"))
      (node (ref "C104") (pin "2") (pinfunction "2_2") (pintype "passive"))
      (node (ref "C105") (pin "2") (pinfunction "2_2") (pintype "passive"))
      (node (ref "C106") (pin "2") (pinfunction "2_2") (pintype "passive"))
      (node (ref "C107") (pin "2") (pinfunction "2_2") (pintype "passive"))
      (node (ref "C108") (pin "2") (pinfunction "2_2") (pintype "passive"))
      (node (ref "C109") (pin "2") (pinfunction "2_2") (pintype "passive"))
      (node (ref "C110") (pin "2") (pinfunction "2_2") (pintype "passive"))
      (node (ref "C111") (pin "2") (pinfunction "2_2") (pintype "passive"))
      (node (ref "C112") (pin "2") (pinfunction "2_2") (pintype "passive"))
      (node (ref "C113") (pin "2") (pinfunction "2_2") (pintype "passive"))
      (node (ref "C114") (pin "2") (pinfunction "2_2") (pintype "passive"))
      (node (ref "C115") (pin "2") (pinfunction "2_2") (pintype "passive"))
      (node (ref "C116") (pin "2") (pinfunction "2_2") (pintype "passive"))
      (node (ref "C117") (pin "2") (pinfunction "2_2") (pintype "passive"))
      (node (ref "R6") (pin "2") (pinfunction "2_2") (pintype "passive"))
      (node (ref "R8") (pin "1") (pinfunction "1_1") (pintype "passive"))
      (node (ref "R9") (pin "1") (pinfunction "1_1") (pintype "passive"))
      (node (ref "U3") (pin "AA10") (pinfunction "VDDQ_AA10") (pintype "passive"))
      (node (ref "U3") (pin "AA3") (pinfunction "VDDQ_AA3") (pintype "passive"))
      (node (ref "U3") (pin "AA5") (pinfunction "VDDQ_AA5") (pintype "passive"))
      (node (ref "U3") (pin "AA8") (pinfunction "VDDQ_AA8") (pintype "passive"))
      (node (ref "U3") (pin "B10") (pinfunction "VDDQ_B10") (pintype "passive"))
      (node (ref "U3") (pin "B3") (pinfunction "VDDQ_B3") (pintype "passive"))
      (node (ref "U3") (pin "B5") (pinfunction "VDDQ_B5") (pintype "passive"))
      (node (ref "U3") (pin "B8") (pinfunction "VDDQ_B8") (pintype "passive"))
      (node (ref "U3") (pin "D1") (pinfunction "VDDQ_D1") (pintype "passive"))
      (node (ref "U3") (pin "D12") (pinfunction "VDDQ_D12") (pintype "passive"))
      (node (ref "U3") (pin "D5") (pinfunction "VDDQ_D5") (pintype "passive"))
      (node (ref "U3") (pin "D8") (pinfunction "VDDQ_D8") (pintype "passive"))
      (node (ref "U3") (pin "F10") (pinfunction "VDDQ_F10") (pintype "passive"))
      (node (ref "U3") (pin "F3") (pinfunction "VDDQ_F3") (pintype "passive"))
      (node (ref "U3") (pin "U10") (pinfunction "VDDQ_U10") (pintype "passive"))
      (node (ref "U3") (pin "U3") (pinfunction "VDDQ_U3") (pintype "passive"))
      (node (ref "U3") (pin "W1") (pinfunction "VDDQ_W1") (pintype "passive"))
      (node (ref "U3") (pin "W12") (pinfunction "VDDQ_W12") (pintype "passive"))
      (node (ref "U3") (pin "W5") (pinfunction "VDDQ_W5") (pintype "passive"))
      (node (ref "U3") (pin "W8") (pinfunction "VDDQ_W8") (pintype "passive"))
    )
    (net (code "70") (name "unconnected-(U3B-DNU1-PadA1)") (class "Default")
      (node (ref "U3") (pin "A1") (pinfunction "DNU1_A1") (pintype "passive+no_connect"))
    )
    (net (code "71") (name "unconnected-(U3B-DNU2-PadA2)") (class "Default")
      (node (ref "U3") (pin "A2") (pinfunction "DNU2_A2") (pintype "passive+no_connect"))
    )
    (net (code "72") (name "unconnected-(U3B-DNU3-PadA11)") (class "Default")
      (node (ref "U3") (pin "A11") (pinfunction "DNU3_A11") (pintype "passive+no_connect"))
    )
    (net (code "73") (name "unconnected-(U3B-DNU4-PadA12)") (class "Default")
      (node (ref "U3") (pin "A12") (pinfunction "DNU4_A12") (pintype "passive+no_connect"))
    )
    (net (code "74") (name "unconnected-(U3B-DNU5-PadB1)") (class "Default")
      (node (ref "U3") (pin "B1") (pinfunction "DNU5_B1") (pintype "passive+no_connect"))
    )
    (net (code "75") (name "unconnected-(U3B-DNU6-PadB12)") (class "Default")
      (node (ref "U3") (pin "B12") (pinfunction "DNU6_B12") (pintype "passive+no_connect"))
    )
    (net (code "76") (name "unconnected-(U3B-DNU7-PadAA1)") (class "Default")
      (node (ref "U3") (pin "AA1") (pinfunction "DNU7_AA1") (pintype "passive+no_connect"))
    )
    (net (code "77") (name "unconnected-(U3B-DNU8-PadAA12)") (class "Default")
      (node (ref "U3") (pin "AA12") (pinfunction "DNU8_AA12") (pintype "passive+no_connect"))
    )
    (net (code "78") (name "unconnected-(U3B-DNU9-PadAB1)") (class "Default")
      (node (ref "U3") (pin "AB1") (pinfunction "DNU9_AB1") (pintype "passive+no_connect"))
    )
    (net (code "79") (name "unconnected-(U3B-DNU10-PadAB2)") (class "Default")
      (node (ref "U3") (pin "AB2") (pinfunction "DNU10_AB2") (pintype "passive+no_connect"))
    )
    (net (code "80") (name "unconnected-(U3B-DNU11-PadAB11)") (class "Default")
      (node (ref "U3") (pin "AB11") (pinfunction "DNU11_AB11") (pintype "passive+no_connect"))
    )
    (net (code "81") (name "unconnected-(U3B-DNU12-PadAB12)") (class "Default")
      (node (ref "U3") (pin "AB12") (pinfunction "DNU12_AB12") (pintype "passive+no_connect"))
    )
    (net (code "82") (name "unconnected-(U3B-DNU13-PadK8)") (class "Default")
      (node (ref "U3") (pin "K8") (pinfunction "DNU13_K8") (pintype "passive+no_connect"))
    )
    (net (code "83") (name "unconnected-(U3B-DNU14-PadN5)") (class "Default")
      (node (ref "U3") (pin "N5") (pinfunction "DNU14_N5") (pintype "passive+no_connect"))
    )
    (net (code "84") (name "unconnected-(U3B-DNU15-PadK5)") (class "Default")
      (node (ref "U3") (pin "K5") (pinfunction "DNU15_K5") (pintype "passive+no_connect"))
    )
    (net (code "85") (name "unconnected-(U3B-DNU16-PadG11)") (class "Default")
      (node (ref "U3") (pin "G11") (pinfunction "DNU16_G11") (pintype "passive+no_connect"))
    )
    (net (code "86") (name "unconnected-(U3B-DNU17-PadN8)") (class "Default")
      (node (ref "U3") (pin "N8") (pinfunction "DNU17_N8") (pintype "passive+no_connect"))
    )
  )
)
